# EXT-1P-1_1016.net
KiCad netlist of a schematic drawn in EAGLE
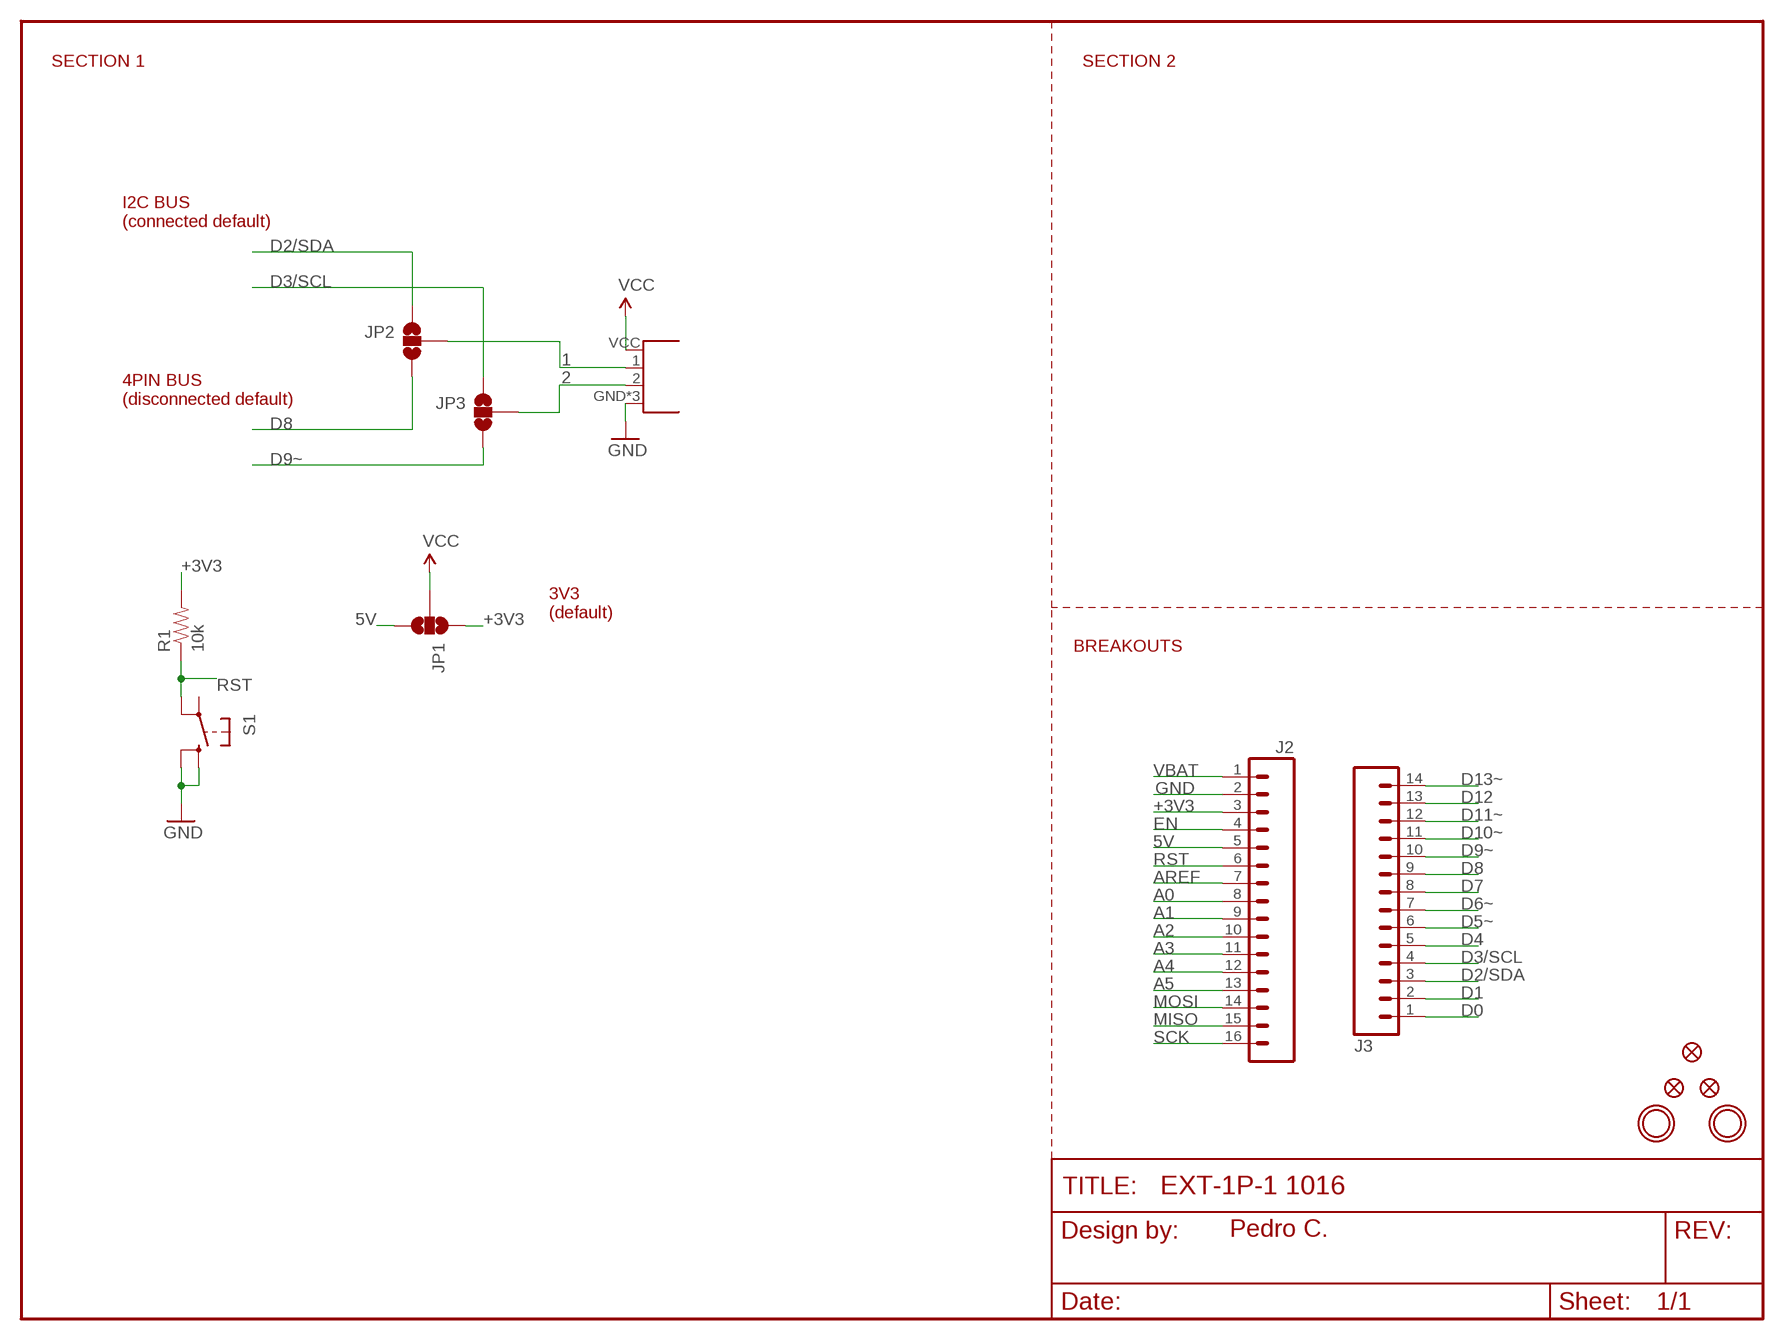
[diagram p0: schematic, sheet 1]

(export (version "E")
  (design (tool "Eeschema 10.0.6"))
  (components
    (comp (ref "FD1")
      (value "FIDUCIALUFIDUCIAL")
      (footprint "eagle-import:MICRO-FIDUCIAL")
      (libsource (lib "eagle-import") (part "FIDUCIALUFIDUCIAL"))
    )
    (comp (ref "FD2")
      (value "FIDUCIALUFIDUCIAL")
      (footprint "eagle-import:MICRO-FIDUCIAL")
      (libsource (lib "eagle-import") (part "FIDUCIALUFIDUCIAL"))
    )
    (comp (ref "FD3")
      (value "FIDUCIALUFIDUCIAL")
      (footprint "eagle-import:MICRO-FIDUCIAL")
      (libsource (lib "eagle-import") (part "FIDUCIALUFIDUCIAL"))
    )
    (comp (ref "J1")
      (value "USB-A-RECP-SINGLE-SMD")
      (footprint "eagle-import:USB-A-RECP-GNC-SMD")
      (libsource (lib "eagle-import") (part "USB-A-RECP-SINGLE-SMD"))
    )
    (comp (ref "J2")
      (value "M16PTH")
      (footprint "eagle-import:1X16")
      (libsource (lib "eagle-import") (part "M16PTH"))
    )
    (comp (ref "J3")
      (value "M14")
      (footprint "eagle-import:1X14")
      (libsource (lib "eagle-import") (part "M14"))
    )
    (comp (ref "JP1")
      (value "SOLDERJUMPER_2WAYPASTE1&2")
      (footprint "eagle-import:SJ_3_PASTE1&2")
      (libsource (lib "eagle-import") (part "SOLDERJUMPER_2WAYPASTE1&2"))
    )
    (comp (ref "JP2")
      (value "SOLDERJUMPER_2WAYPASTE1&2")
      (footprint "eagle-import:SJ_3_PASTE1&2")
      (libsource (lib "eagle-import") (part "SOLDERJUMPER_2WAYPASTE1&2"))
    )
    (comp (ref "JP3")
      (value "SOLDERJUMPER_2WAYPASTE1&2")
      (footprint "eagle-import:SJ_3_PASTE1&2")
      (libsource (lib "eagle-import") (part "SOLDERJUMPER_2WAYPASTE1&2"))
    )
    (comp (ref "MP1")
      (value "MOUNTINGHOLE2.5_THICK")
      (footprint "eagle-import:MOUNTINGHOLE_2.5_PLATED_THICK")
      (libsource (lib "eagle-import") (part "MOUNTINGHOLE2.5_THICK"))
    )
    (comp (ref "MP2")
      (value "MOUNTINGHOLE2.5_THICK")
      (footprint "eagle-import:MOUNTINGHOLE_2.5_PLATED_THICK")
      (libsource (lib "eagle-import") (part "MOUNTINGHOLE2.5_THICK"))
    )
    (comp (ref "R1")
      (value "10k")
      (footprint "eagle-import:0603-RES")
      (libsource (lib "eagle-import") (part "RESISTOR0603-RES"))
    )
    (comp (ref "S1")
      (value "TACT-SWITCH")
      (footprint "eagle-import:TACT-SWITCH")
      (libsource (lib "eagle-import") (part "TACT-SWITCH"))
    )
  )
  (nets
    (net (code "1") (name "/+3V3") (class "Default")
      (node (ref "J2") (pin "3") (pinfunction "3_3") (pintype "passive"))
      (node (ref "JP1") (pin "1") (pinfunction "1_1") (pintype "passive"))
      (node (ref "R1") (pin "2") (pinfunction "2_2") (pintype "passive"))
    )
    (net (code "2") (name "/1") (class "Default")
      (node (ref "J1") (pin "1") (pinfunction "1_1") (pintype "bidirectional"))
      (node (ref "JP2") (pin "2") (pinfunction "2_2") (pintype "passive"))
    )
    (net (code "3") (name "/2") (class "Default")
      (node (ref "J1") (pin "2") (pinfunction "2_2") (pintype "bidirectional"))
      (node (ref "JP3") (pin "2") (pinfunction "2_2") (pintype "passive"))
    )
    (net (code "4") (name "/5V") (class "Default")
      (node (ref "J2") (pin "5") (pinfunction "5_5") (pintype "passive"))
      (node (ref "JP1") (pin "3") (pinfunction "3_3") (pintype "passive"))
    )
    (net (code "5") (name "/A0") (class "Default")
      (node (ref "J2") (pin "8") (pinfunction "8_8") (pintype "passive"))
    )
    (net (code "6") (name "/A1") (class "Default")
      (node (ref "J2") (pin "9") (pinfunction "9_9") (pintype "passive"))
    )
    (net (code "7") (name "/A2") (class "Default")
      (node (ref "J2") (pin "10") (pinfunction "10_10") (pintype "passive"))
    )
    (net (code "8") (name "/A3") (class "Default")
      (node (ref "J2") (pin "11") (pinfunction "11_11") (pintype "passive"))
    )
    (net (code "9") (name "/A4") (class "Default")
      (node (ref "J2") (pin "12") (pinfunction "12_12") (pintype "passive"))
    )
    (net (code "10") (name "/A5") (class "Default")
      (node (ref "J2") (pin "13") (pinfunction "13_13") (pintype "passive"))
    )
    (net (code "11") (name "/AREF") (class "Default")
      (node (ref "J2") (pin "7") (pinfunction "7_7") (pintype "passive"))
    )
    (net (code "12") (name "/D0") (class "Default")
      (node (ref "J3") (pin "1") (pinfunction "1_1") (pintype "passive"))
    )
    (net (code "13") (name "/D1") (class "Default")
      (node (ref "J3") (pin "2") (pinfunction "2_2") (pintype "passive"))
    )
    (net (code "14") (name "/D2{slash}SDA") (class "Default")
      (node (ref "J3") (pin "3") (pinfunction "3_3") (pintype "passive"))
      (node (ref "JP2") (pin "1") (pinfunction "1_1") (pintype "passive"))
    )
    (net (code "15") (name "/D3{slash}SCL") (class "Default")
      (node (ref "J3") (pin "4") (pinfunction "4_4") (pintype "passive"))
      (node (ref "JP3") (pin "1") (pinfunction "1_1") (pintype "passive"))
    )
    (net (code "16") (name "/D4") (class "Default")
      (node (ref "J3") (pin "5") (pinfunction "5_5") (pintype "passive"))
    )
    (net (code "17") (name "/D5~{}") (class "Default")
      (node (ref "J3") (pin "6") (pinfunction "6_6") (pintype "passive"))
    )
    (net (code "18") (name "/D6~{}") (class "Default")
      (node (ref "J3") (pin "7") (pinfunction "7_7") (pintype "passive"))
    )
    (net (code "19") (name "/D7") (class "Default")
      (node (ref "J3") (pin "8") (pinfunction "8_8") (pintype "passive"))
    )
    (net (code "20") (name "/D8") (class "Default")
      (node (ref "J3") (pin "9") (pinfunction "9_9") (pintype "passive"))
      (node (ref "JP2") (pin "3") (pinfunction "3_3") (pintype "passive"))
    )
    (net (code "21") (name "/D9~{}") (class "Default")
      (node (ref "J3") (pin "10") (pinfunction "10_10") (pintype "passive"))
      (node (ref "JP3") (pin "3") (pinfunction "3_3") (pintype "passive"))
    )
    (net (code "22") (name "/D10~{}") (class "Default")
      (node (ref "J3") (pin "11") (pinfunction "11_11") (pintype "passive"))
    )
    (net (code "23") (name "/D11~{}") (class "Default")
      (node (ref "J3") (pin "12") (pinfunction "12_12") (pintype "passive"))
    )
    (net (code "24") (name "/D12") (class "Default")
      (node (ref "J3") (pin "13") (pinfunction "13_13") (pintype "passive"))
    )
    (net (code "25") (name "/D13~{}") (class "Default")
      (node (ref "J3") (pin "14") (pinfunction "14_14") (pintype "passive"))
    )
    (net (code "26") (name "/EN") (class "Default")
      (node (ref "J2") (pin "4") (pinfunction "4_4") (pintype "passive"))
    )
    (net (code "27") (name "/MISO") (class "Default")
      (node (ref "J2") (pin "15") (pinfunction "15_15") (pintype "passive"))
    )
    (net (code "28") (name "/MOSI") (class "Default")
      (node (ref "J2") (pin "14") (pinfunction "14_14") (pintype "passive"))
    )
    (net (code "29") (name "/RST") (class "Default")
      (node (ref "J2") (pin "6") (pinfunction "6_6") (pintype "passive"))
      (node (ref "R1") (pin "1") (pinfunction "1_1") (pintype "passive"))
      (node (ref "S1") (pin "2") (pinfunction "2_2") (pintype "passive"))
    )
    (net (code "30") (name "/SCK") (class "Default")
      (node (ref "J2") (pin "16") (pinfunction "16_16") (pintype "passive"))
    )
    (net (code "31") (name "/VBAT") (class "Default")
      (node (ref "J2") (pin "1") (pinfunction "1_1") (pintype "passive"))
    )
    (net (code "32") (name "GND") (class "Default")
      (node (ref "J1") (pin "GND") (pinfunction "GND_GND") (pintype "bidirectional"))
      (node (ref "J1") (pin "GND1") (pinfunction "GND_GND1") (pintype "bidirectional"))
      (node (ref "J1") (pin "GND2") (pinfunction "GND_GND2") (pintype "bidirectional"))
      (node (ref "J2") (pin "2") (pinfunction "2_2") (pintype "passive"))
      (node (ref "S1") (pin "3") (pinfunction "3_3") (pintype "passive"))
      (node (ref "S1") (pin "4") (pinfunction "4_4") (pintype "passive"))
    )
    (net (code "33") (name "VCC") (class "Default")
      (node (ref "J1") (pin "VCC") (pinfunction "VCC_VCC") (pintype "bidirectional"))
      (node (ref "JP1") (pin "2") (pinfunction "2_2") (pintype "passive"))
    )
    (net (code "34") (name "unconnected-(S1-Pad1)") (class "Default")
      (node (ref "S1") (pin "1") (pinfunction "1_1") (pintype "passive"))
    )
  )
)
